# TOUv2.net
KiCad netlist of a schematic drawn in EAGLE
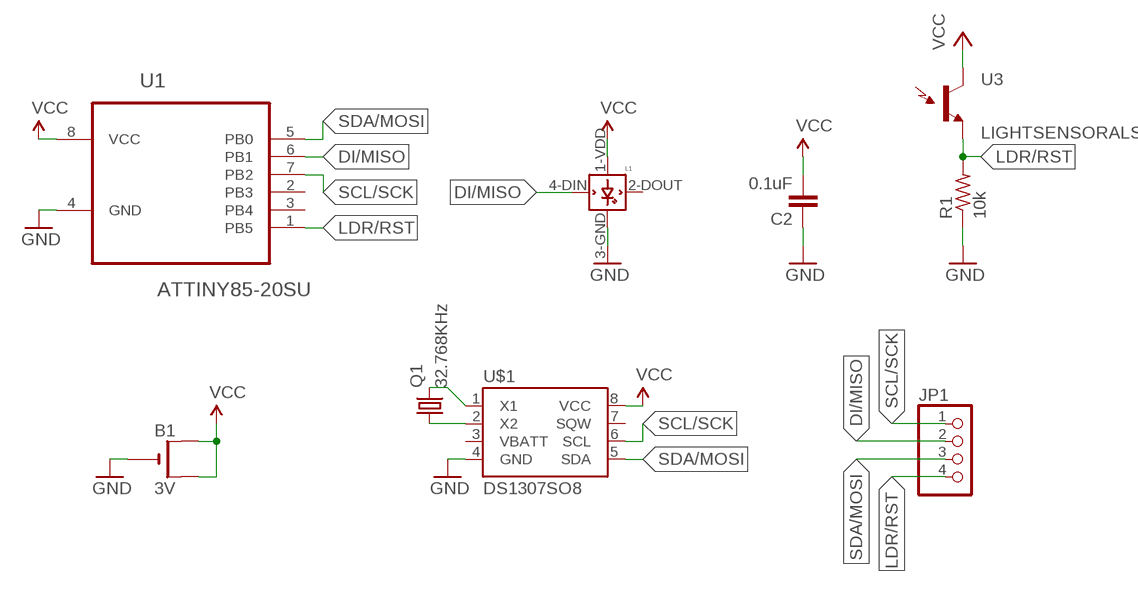
[diagram p0: schematic, sheet 1]

(export (version "E")
  (design (tool "Eeschema 10.0.6"))
  (components
    (comp (ref "B1")
      (value "3V")
      (footprint "eagle-import:CR2032-THRU")
      (libsource (lib "eagle-import") (part "CR2032THM"))
    )
    (comp (ref "C2")
      (value "0.1uF")
      (footprint "eagle-import:0603-CAP")
      (libsource (lib "eagle-import") (part "CAP0603-CAP"))
    )
    (comp (ref "JP1")
      (value "PINHD-1X4")
      (footprint "eagle-import:1X04")
      (libsource (lib "eagle-import") (part "PINHD-1X4"))
    )
    (comp (ref "L1")
      (value "WS2812B")
      (footprint "eagle-import:WS2812B")
      (libsource (lib "eagle-import") (part "WS2812B"))
    )
    (comp (ref "Q1")
      (value "32.768KHz")
      (footprint "eagle-import:CTS406")
      (libsource (lib "eagle-import") (part "CRYSTALCTS406"))
    )
    (comp (ref "R1")
      (value "10k")
      (footprint "eagle-import:R0402")
      (libsource (lib "eagle-import") (part "R-US_R0402"))
    )
    (comp (ref "U$1")
      (value "DS1307SO8")
      (footprint "eagle-import:SO08")
      (libsource (lib "eagle-import") (part "DS1307SO8"))
    )
    (comp (ref "U1")
      (value "ATTINY85-20SU")
      (footprint "eagle-import:SOIC127P798X216-8N")
      (libsource (lib "eagle-import") (part "ATTINY85-20SU"))
    )
    (comp (ref "U3")
      (value "LIGHTSENSORALS")
      (footprint "eagle-import:ALS-PT19")
      (libsource (lib "eagle-import") (part "LIGHTSENSORALS"))
    )
  )
  (nets
    (net (code "1") (name "DI{slash}MISO") (class "Default")
      (node (ref "JP1") (pin "2") (pinfunction "2_2") (pintype "passive"))
      (node (ref "L1") (pin "4-DIN") (pinfunction "DIN_4-DIN") (pintype "input"))
      (node (ref "U1") (pin "6") (pinfunction "PB1_6") (pintype "bidirectional"))
    )
    (net (code "2") (name "GND") (class "Default")
      (node (ref "B1") (pin "-") (pinfunction "-_-") (pintype "passive"))
      (node (ref "C2") (pin "1") (pinfunction "1_1") (pintype "passive"))
      (node (ref "L1") (pin "3-GND") (pinfunction "GND_3-GND") (pintype "bidirectional"))
      (node (ref "R1") (pin "1") (pinfunction "1_1") (pintype "passive"))
      (node (ref "U$1") (pin "4") (pinfunction "GND_4") (pintype "bidirectional"))
      (node (ref "U1") (pin "4") (pinfunction "GND_4") (pintype "passive"))
    )
    (net (code "3") (name "LDR{slash}RST") (class "Default")
      (node (ref "JP1") (pin "4") (pinfunction "4_4") (pintype "passive"))
      (node (ref "R1") (pin "2") (pinfunction "2_2") (pintype "passive"))
      (node (ref "U1") (pin "1") (pinfunction "PB5_1") (pintype "bidirectional"))
      (node (ref "U3") (pin "E") (pinfunction "E1_E") (pintype "passive"))
    )
    (net (code "4") (name "Net-(Q1-2)") (class "Default")
      (node (ref "Q1") (pin "3") (pinfunction "2_3") (pintype "passive"))
      (node (ref "U$1") (pin "1") (pinfunction "X1_1") (pintype "bidirectional"))
    )
    (net (code "5") (name "Net-(U$1-X2)") (class "Default")
      (node (ref "Q1") (pin "1") (pinfunction "1_1") (pintype "passive"))
      (node (ref "U$1") (pin "2") (pinfunction "X2_2") (pintype "bidirectional"))
    )
    (net (code "6") (name "SCL{slash}SCK") (class "Default")
      (node (ref "JP1") (pin "1") (pinfunction "1_1") (pintype "passive"))
      (node (ref "U$1") (pin "6") (pinfunction "SCL_6") (pintype "bidirectional"))
      (node (ref "U1") (pin "7") (pinfunction "PB2_7") (pintype "bidirectional"))
    )
    (net (code "7") (name "SDA{slash}MOSI") (class "Default")
      (node (ref "JP1") (pin "3") (pinfunction "3_3") (pintype "passive"))
      (node (ref "U$1") (pin "5") (pinfunction "SDA_5") (pintype "bidirectional"))
      (node (ref "U1") (pin "5") (pinfunction "PB0_5") (pintype "bidirectional"))
    )
    (net (code "8") (name "VCC") (class "Default")
      (node (ref "B1") (pin "+1") (pinfunction "+_+1") (pintype "passive"))
      (node (ref "B1") (pin "+2") (pinfunction "+1_+2") (pintype "passive"))
      (node (ref "C2") (pin "2") (pinfunction "2_2") (pintype "passive"))
      (node (ref "L1") (pin "1-VDD") (pinfunction "VDD_1-VDD") (pintype "bidirectional"))
      (node (ref "U$1") (pin "8") (pinfunction "VCC_8") (pintype "bidirectional"))
      (node (ref "U1") (pin "8") (pinfunction "VCC_8") (pintype "power_in"))
      (node (ref "U3") (pin "C") (pinfunction "C1_C") (pintype "passive"))
    )
    (net (code "9") (name "unconnected-(L1-DOUT-Pad2-DOUT)") (class "Default")
      (node (ref "L1") (pin "2-DOUT") (pinfunction "DOUT_2-DOUT") (pintype "output"))
    )
    (net (code "10") (name "unconnected-(U$1-SQW-Pad7)") (class "Default")
      (node (ref "U$1") (pin "7") (pinfunction "SQW_7") (pintype "bidirectional"))
    )
    (net (code "11") (name "unconnected-(U$1-VBATT-Pad3)") (class "Default")
      (node (ref "U$1") (pin "3") (pinfunction "VBATT_3") (pintype "bidirectional"))
    )
    (net (code "12") (name "unconnected-(U1-PB3-Pad2)") (class "Default")
      (node (ref "U1") (pin "2") (pinfunction "PB3_2") (pintype "bidirectional"))
    )
    (net (code "13") (name "unconnected-(U1-PB4-Pad3)") (class "Default")
      (node (ref "U1") (pin "3") (pinfunction "PB4_3") (pintype "bidirectional"))
    )
  )
)
